# MCP23S17-v2.net
KiCad netlist of a schematic drawn in EAGLE
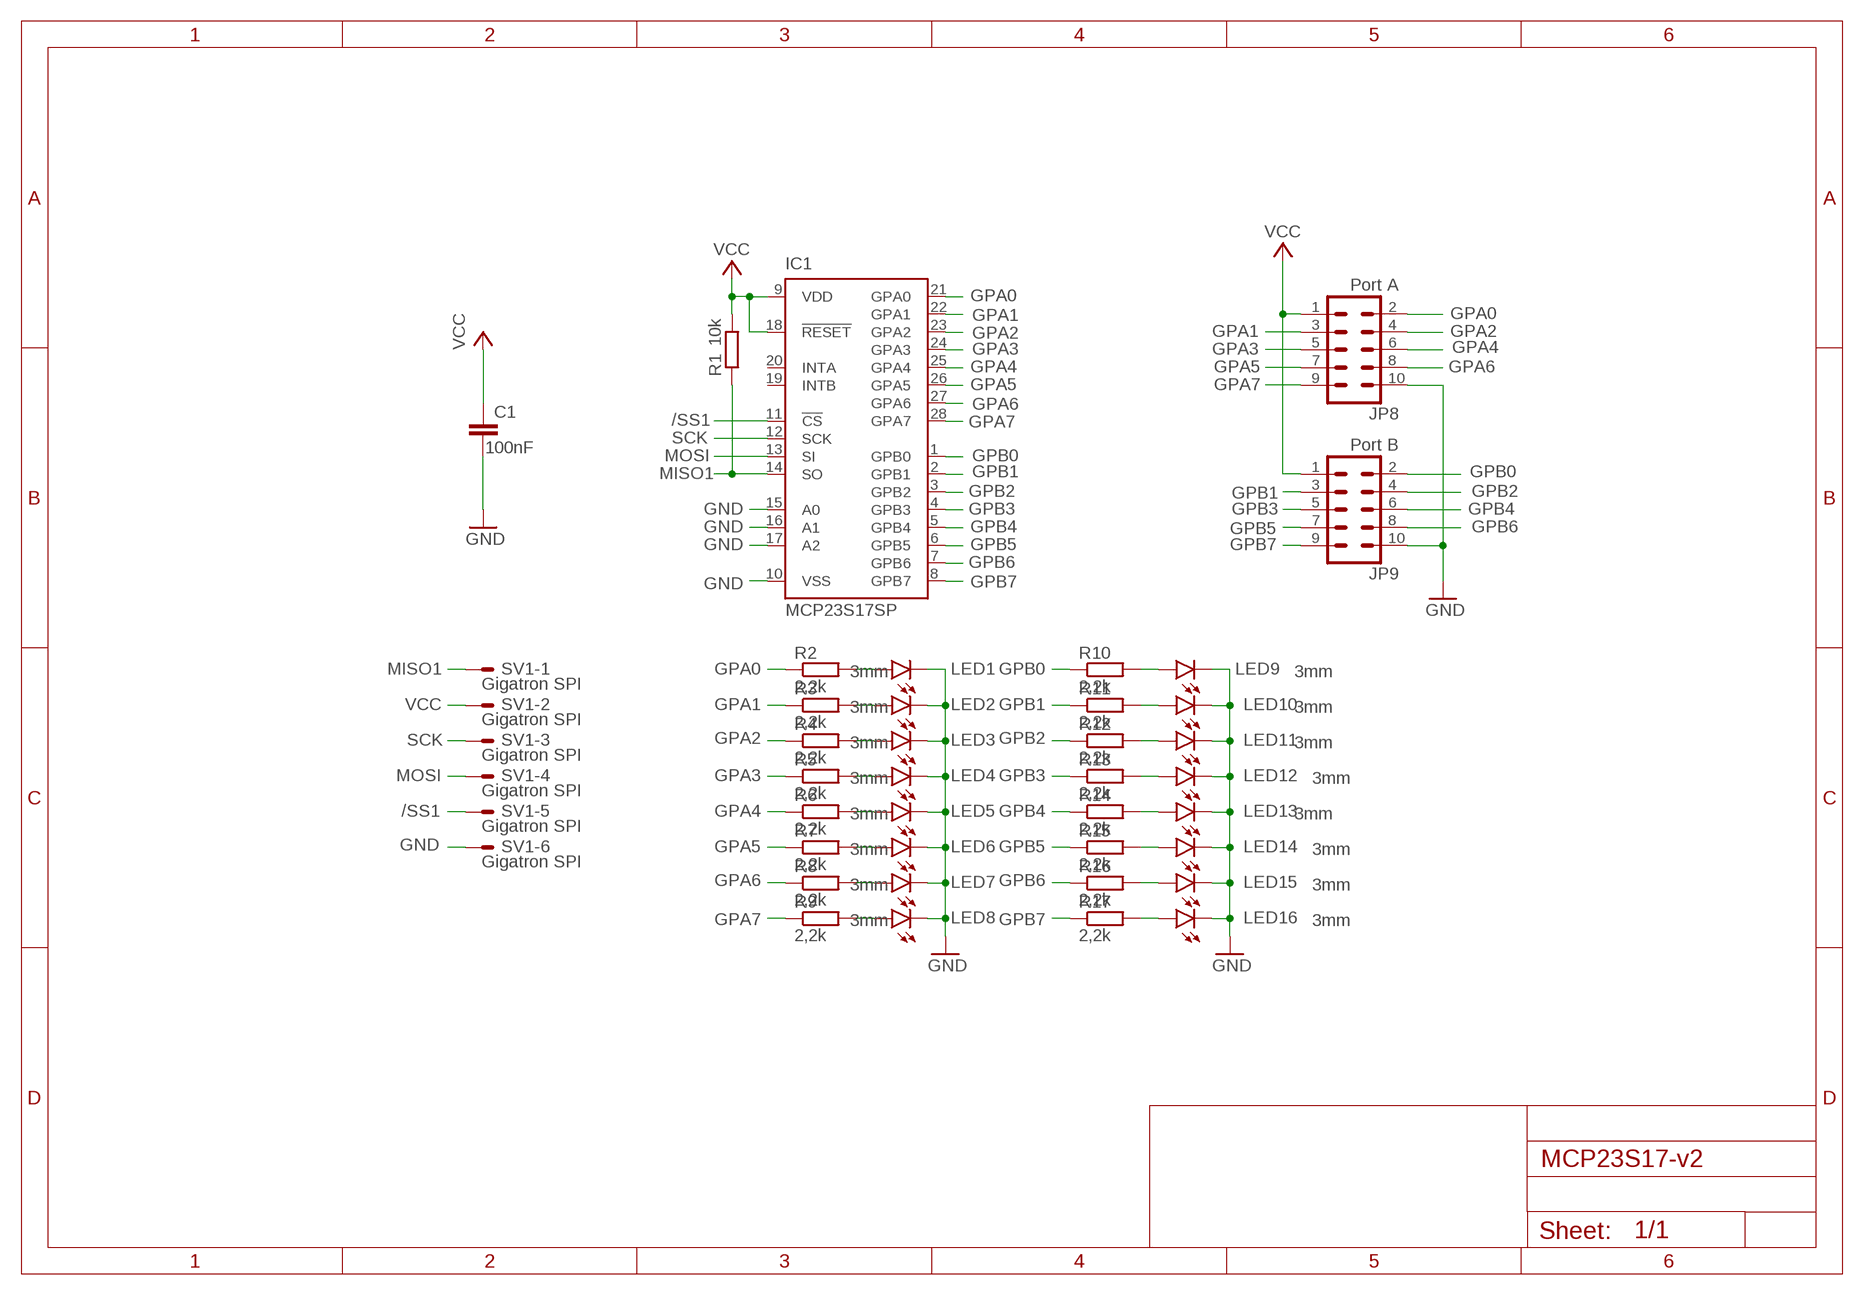
[diagram p0: schematic, sheet 1]

(export (version "E")
  (design (tool "Eeschema 10.0.6"))
  (components
    (comp (ref "C1")
      (value "100nF")
      (footprint "eagle-import:C5B2.5")
      (libsource (lib "eagle-import") (part "C5/2.5"))
    )
    (comp (ref "IC1")
      (value "MCP23S17SP")
      (footprint "eagle-import:DIL28-3")
      (fields (field (name "MF") "MICROCHIP") (field (name "MPN") "MCP23S17-E/SP"))
      (libsource (lib "eagle-import") (part "MCP23S17SP"))
    )
    (comp (ref "JP8")
      (value "Port A")
      (footprint "eagle-import:ML10")
      (libsource (lib "eagle-import") (part "ML10"))
    )
    (comp (ref "JP9")
      (value "Port B")
      (footprint "eagle-import:ML10")
      (libsource (lib "eagle-import") (part "ML10"))
    )
    (comp (ref "LED1")
      (value "3mm")
      (footprint "eagle-import:LED3MM")
      (libsource (lib "eagle-import") (part "LED3MM"))
    )
    (comp (ref "LED2")
      (value "3mm")
      (footprint "eagle-import:LED3MM")
      (libsource (lib "eagle-import") (part "LED3MM"))
    )
    (comp (ref "LED3")
      (value "3mm")
      (footprint "eagle-import:LED3MM")
      (libsource (lib "eagle-import") (part "LED3MM"))
    )
    (comp (ref "LED4")
      (value "3mm")
      (footprint "eagle-import:LED3MM")
      (libsource (lib "eagle-import") (part "LED3MM"))
    )
    (comp (ref "LED5")
      (value "3mm")
      (footprint "eagle-import:LED3MM")
      (libsource (lib "eagle-import") (part "LED3MM"))
    )
    (comp (ref "LED6")
      (value "3mm")
      (footprint "eagle-import:LED3MM")
      (libsource (lib "eagle-import") (part "LED3MM"))
    )
    (comp (ref "LED7")
      (value "3mm")
      (footprint "eagle-import:LED3MM")
      (libsource (lib "eagle-import") (part "LED3MM"))
    )
    (comp (ref "LED8")
      (value "3mm")
      (footprint "eagle-import:LED3MM")
      (libsource (lib "eagle-import") (part "LED3MM"))
    )
    (comp (ref "LED9")
      (value "3mm")
      (footprint "eagle-import:LED3MM")
      (libsource (lib "eagle-import") (part "LED3MM"))
    )
    (comp (ref "LED10")
      (value "3mm")
      (footprint "eagle-import:LED3MM")
      (libsource (lib "eagle-import") (part "LED3MM"))
    )
    (comp (ref "LED11")
      (value "3mm")
      (footprint "eagle-import:LED3MM")
      (libsource (lib "eagle-import") (part "LED3MM"))
    )
    (comp (ref "LED12")
      (value "3mm")
      (footprint "eagle-import:LED3MM")
      (libsource (lib "eagle-import") (part "LED3MM"))
    )
    (comp (ref "LED13")
      (value "3mm")
      (footprint "eagle-import:LED3MM")
      (libsource (lib "eagle-import") (part "LED3MM"))
    )
    (comp (ref "LED14")
      (value "3mm")
      (footprint "eagle-import:LED3MM")
      (libsource (lib "eagle-import") (part "LED3MM"))
    )
    (comp (ref "LED15")
      (value "3mm")
      (footprint "eagle-import:LED3MM")
      (libsource (lib "eagle-import") (part "LED3MM"))
    )
    (comp (ref "LED16")
      (value "3mm")
      (footprint "eagle-import:LED3MM")
      (libsource (lib "eagle-import") (part "LED3MM"))
    )
    (comp (ref "R1")
      (value "10k")
      (footprint "eagle-import:0207_10")
      (libsource (lib "eagle-import") (part "R-EU_0207/10"))
    )
    (comp (ref "R2")
      (value "2,2k")
      (footprint "eagle-import:0207_10")
      (libsource (lib "eagle-import") (part "R-EU_0207/10"))
    )
    (comp (ref "R3")
      (value "2,2k")
      (footprint "eagle-import:0207_10")
      (libsource (lib "eagle-import") (part "R-EU_0207/10"))
    )
    (comp (ref "R4")
      (value "2,2k")
      (footprint "eagle-import:0207_10")
      (libsource (lib "eagle-import") (part "R-EU_0207/10"))
    )
    (comp (ref "R5")
      (value "2,2k")
      (footprint "eagle-import:0207_10")
      (libsource (lib "eagle-import") (part "R-EU_0207/10"))
    )
    (comp (ref "R6")
      (value "2,2k")
      (footprint "eagle-import:0207_10")
      (libsource (lib "eagle-import") (part "R-EU_0207/10"))
    )
    (comp (ref "R7")
      (value "2,2k")
      (footprint "eagle-import:0207_10")
      (libsource (lib "eagle-import") (part "R-EU_0207/10"))
    )
    (comp (ref "R8")
      (value "2,2k")
      (footprint "eagle-import:0207_10")
      (libsource (lib "eagle-import") (part "R-EU_0207/10"))
    )
    (comp (ref "R9")
      (value "2,2k")
      (footprint "eagle-import:0207_10")
      (libsource (lib "eagle-import") (part "R-EU_0207/10"))
    )
    (comp (ref "R10")
      (value "2,2k")
      (footprint "eagle-import:0207_10")
      (libsource (lib "eagle-import") (part "R-EU_0207/10"))
    )
    (comp (ref "R11")
      (value "2,2k")
      (footprint "eagle-import:0207_10")
      (libsource (lib "eagle-import") (part "R-EU_0207/10"))
    )
    (comp (ref "R12")
      (value "2,2k")
      (footprint "eagle-import:0207_10")
      (libsource (lib "eagle-import") (part "R-EU_0207/10"))
    )
    (comp (ref "R13")
      (value "2,2k")
      (footprint "eagle-import:0207_10")
      (libsource (lib "eagle-import") (part "R-EU_0207/10"))
    )
    (comp (ref "R14")
      (value "2,2k")
      (footprint "eagle-import:0207_10")
      (libsource (lib "eagle-import") (part "R-EU_0207/10"))
    )
    (comp (ref "R15")
      (value "2,2k")
      (footprint "eagle-import:0207_10")
      (libsource (lib "eagle-import") (part "R-EU_0207/10"))
    )
    (comp (ref "R16")
      (value "2,2k")
      (footprint "eagle-import:0207_10")
      (libsource (lib "eagle-import") (part "R-EU_0207/10"))
    )
    (comp (ref "R17")
      (value "2,2k")
      (footprint "eagle-import:0207_10")
      (libsource (lib "eagle-import") (part "R-EU_0207/10"))
    )
    (comp (ref "SV1")
      (value "Gigatron SPI")
      (footprint "eagle-import:ML6")
      (libsource (lib "eagle-import") (part "ML6E"))
    )
  )
  (nets
    (net (code "1") (name "/GPA0") (class "Default")
      (node (ref "IC1") (pin "21") (pinfunction "GPA0_21") (pintype "bidirectional"))
      (node (ref "JP8") (pin "2") (pinfunction "2_2") (pintype "passive"))
      (node (ref "R2") (pin "1") (pinfunction "1_1") (pintype "passive"))
    )
    (net (code "2") (name "/GPA1") (class "Default")
      (node (ref "IC1") (pin "22") (pinfunction "GPA1_22") (pintype "bidirectional"))
      (node (ref "JP8") (pin "3") (pinfunction "3_3") (pintype "passive"))
      (node (ref "R3") (pin "1") (pinfunction "1_1") (pintype "passive"))
    )
    (net (code "3") (name "/GPA2") (class "Default")
      (node (ref "IC1") (pin "23") (pinfunction "GPA2_23") (pintype "bidirectional"))
      (node (ref "JP8") (pin "4") (pinfunction "4_4") (pintype "passive"))
      (node (ref "R4") (pin "1") (pinfunction "1_1") (pintype "passive"))
    )
    (net (code "4") (name "/GPA3") (class "Default")
      (node (ref "IC1") (pin "24") (pinfunction "GPA3_24") (pintype "bidirectional"))
      (node (ref "JP8") (pin "5") (pinfunction "5_5") (pintype "passive"))
      (node (ref "R5") (pin "1") (pinfunction "1_1") (pintype "passive"))
    )
    (net (code "5") (name "/GPA4") (class "Default")
      (node (ref "IC1") (pin "25") (pinfunction "GPA4_25") (pintype "bidirectional"))
      (node (ref "JP8") (pin "6") (pinfunction "6_6") (pintype "passive"))
      (node (ref "R6") (pin "1") (pinfunction "1_1") (pintype "passive"))
    )
    (net (code "6") (name "/GPA5") (class "Default")
      (node (ref "IC1") (pin "26") (pinfunction "GPA5_26") (pintype "bidirectional"))
      (node (ref "JP8") (pin "7") (pinfunction "7_7") (pintype "passive"))
      (node (ref "R7") (pin "1") (pinfunction "1_1") (pintype "passive"))
    )
    (net (code "7") (name "/GPA6") (class "Default")
      (node (ref "IC1") (pin "27") (pinfunction "GPA6_27") (pintype "bidirectional"))
      (node (ref "JP8") (pin "8") (pinfunction "8_8") (pintype "passive"))
      (node (ref "R8") (pin "1") (pinfunction "1_1") (pintype "passive"))
    )
    (net (code "8") (name "/GPA7") (class "Default")
      (node (ref "IC1") (pin "28") (pinfunction "GPA7_28") (pintype "bidirectional"))
      (node (ref "JP8") (pin "9") (pinfunction "9_9") (pintype "passive"))
      (node (ref "R9") (pin "1") (pinfunction "1_1") (pintype "passive"))
    )
    (net (code "9") (name "/GPB0") (class "Default")
      (node (ref "IC1") (pin "1") (pinfunction "GPB0_1") (pintype "bidirectional"))
      (node (ref "JP9") (pin "2") (pinfunction "2_2") (pintype "passive"))
      (node (ref "R10") (pin "1") (pinfunction "1_1") (pintype "passive"))
    )
    (net (code "10") (name "/GPB1") (class "Default")
      (node (ref "IC1") (pin "2") (pinfunction "GPB1_2") (pintype "bidirectional"))
      (node (ref "JP9") (pin "3") (pinfunction "3_3") (pintype "passive"))
      (node (ref "R11") (pin "1") (pinfunction "1_1") (pintype "passive"))
    )
    (net (code "11") (name "/GPB2") (class "Default")
      (node (ref "IC1") (pin "3") (pinfunction "GPB2_3") (pintype "bidirectional"))
      (node (ref "JP9") (pin "4") (pinfunction "4_4") (pintype "passive"))
      (node (ref "R12") (pin "1") (pinfunction "1_1") (pintype "passive"))
    )
    (net (code "12") (name "/GPB3") (class "Default")
      (node (ref "IC1") (pin "4") (pinfunction "GPB3_4") (pintype "bidirectional"))
      (node (ref "JP9") (pin "5") (pinfunction "5_5") (pintype "passive"))
      (node (ref "R13") (pin "1") (pinfunction "1_1") (pintype "passive"))
    )
    (net (code "13") (name "/GPB4") (class "Default")
      (node (ref "IC1") (pin "5") (pinfunction "GPB4_5") (pintype "bidirectional"))
      (node (ref "JP9") (pin "6") (pinfunction "6_6") (pintype "passive"))
      (node (ref "R14") (pin "1") (pinfunction "1_1") (pintype "passive"))
    )
    (net (code "14") (name "/GPB5") (class "Default")
      (node (ref "IC1") (pin "6") (pinfunction "GPB5_6") (pintype "bidirectional"))
      (node (ref "JP9") (pin "7") (pinfunction "7_7") (pintype "passive"))
      (node (ref "R15") (pin "1") (pinfunction "1_1") (pintype "passive"))
    )
    (net (code "15") (name "/GPB6") (class "Default")
      (node (ref "IC1") (pin "7") (pinfunction "GPB6_7") (pintype "bidirectional"))
      (node (ref "JP9") (pin "8") (pinfunction "8_8") (pintype "passive"))
      (node (ref "R16") (pin "1") (pinfunction "1_1") (pintype "passive"))
    )
    (net (code "16") (name "/GPB7") (class "Default")
      (node (ref "IC1") (pin "8") (pinfunction "GPB7_8") (pintype "bidirectional"))
      (node (ref "JP9") (pin "9") (pinfunction "9_9") (pintype "passive"))
      (node (ref "R17") (pin "1") (pinfunction "1_1") (pintype "passive"))
    )
    (net (code "17") (name "/MISO1") (class "Default")
      (node (ref "IC1") (pin "14") (pinfunction "SO_14") (pintype "output"))
      (node (ref "R1") (pin "1") (pinfunction "1_1") (pintype "passive"))
      (node (ref "SV1") (pin "1") (pinfunction "S_1") (pintype "passive"))
    )
    (net (code "18") (name "/MOSI") (class "Default")
      (node (ref "IC1") (pin "13") (pinfunction "SI_13") (pintype "input"))
      (node (ref "SV1") (pin "4") (pinfunction "S_4") (pintype "passive"))
    )
    (net (code "19") (name "/SCK") (class "Default")
      (node (ref "IC1") (pin "12") (pinfunction "SCK_12") (pintype "input"))
      (node (ref "SV1") (pin "3") (pinfunction "S_3") (pintype "passive"))
    )
    (net (code "20") (name "/{slash}SS1") (class "Default")
      (node (ref "IC1") (pin "11") (pinfunction "~{CS}_11") (pintype "input"))
      (node (ref "SV1") (pin "5") (pinfunction "S_5") (pintype "passive"))
    )
    (net (code "21") (name "GND") (class "Default")
      (node (ref "C1") (pin "2") (pinfunction "2_2") (pintype "passive"))
      (node (ref "IC1") (pin "10") (pinfunction "VSS_10") (pintype "power_in"))
      (node (ref "IC1") (pin "15") (pinfunction "A0_15") (pintype "input"))
      (node (ref "IC1") (pin "16") (pinfunction "A1_16") (pintype "input"))
      (node (ref "IC1") (pin "17") (pinfunction "A2_17") (pintype "input"))
      (node (ref "JP8") (pin "10") (pinfunction "10_10") (pintype "passive"))
      (node (ref "JP9") (pin "10") (pinfunction "10_10") (pintype "passive"))
      (node (ref "LED1") (pin "K") (pinfunction "C_K") (pintype "passive"))
      (node (ref "LED10") (pin "K") (pinfunction "C_K") (pintype "passive"))
      (node (ref "LED11") (pin "K") (pinfunction "C_K") (pintype "passive"))
      (node (ref "LED12") (pin "K") (pinfunction "C_K") (pintype "passive"))
      (node (ref "LED13") (pin "K") (pinfunction "C_K") (pintype "passive"))
      (node (ref "LED14") (pin "K") (pinfunction "C_K") (pintype "passive"))
      (node (ref "LED15") (pin "K") (pinfunction "C_K") (pintype "passive"))
      (node (ref "LED16") (pin "K") (pinfunction "C_K") (pintype "passive"))
      (node (ref "LED2") (pin "K") (pinfunction "C_K") (pintype "passive"))
      (node (ref "LED3") (pin "K") (pinfunction "C_K") (pintype "passive"))
      (node (ref "LED4") (pin "K") (pinfunction "C_K") (pintype "passive"))
      (node (ref "LED5") (pin "K") (pinfunction "C_K") (pintype "passive"))
      (node (ref "LED6") (pin "K") (pinfunction "C_K") (pintype "passive"))
      (node (ref "LED7") (pin "K") (pinfunction "C_K") (pintype "passive"))
      (node (ref "LED8") (pin "K") (pinfunction "C_K") (pintype "passive"))
      (node (ref "LED9") (pin "K") (pinfunction "C_K") (pintype "passive"))
      (node (ref "SV1") (pin "6") (pinfunction "S_6") (pintype "passive"))
    )
    (net (code "22") (name "Net-(LED1-PadA)") (class "Default")
      (node (ref "LED1") (pin "A") (pinfunction "A_A") (pintype "passive"))
      (node (ref "R2") (pin "2") (pinfunction "2_2") (pintype "passive"))
    )
    (net (code "23") (name "Net-(LED2-PadA)") (class "Default")
      (node (ref "LED2") (pin "A") (pinfunction "A_A") (pintype "passive"))
      (node (ref "R3") (pin "2") (pinfunction "2_2") (pintype "passive"))
    )
    (net (code "24") (name "Net-(LED3-PadA)") (class "Default")
      (node (ref "LED3") (pin "A") (pinfunction "A_A") (pintype "passive"))
      (node (ref "R4") (pin "2") (pinfunction "2_2") (pintype "passive"))
    )
    (net (code "25") (name "Net-(LED4-PadA)") (class "Default")
      (node (ref "LED4") (pin "A") (pinfunction "A_A") (pintype "passive"))
      (node (ref "R5") (pin "2") (pinfunction "2_2") (pintype "passive"))
    )
    (net (code "26") (name "Net-(LED5-PadA)") (class "Default")
      (node (ref "LED5") (pin "A") (pinfunction "A_A") (pintype "passive"))
      (node (ref "R6") (pin "2") (pinfunction "2_2") (pintype "passive"))
    )
    (net (code "27") (name "Net-(LED6-PadA)") (class "Default")
      (node (ref "LED6") (pin "A") (pinfunction "A_A") (pintype "passive"))
      (node (ref "R7") (pin "2") (pinfunction "2_2") (pintype "passive"))
    )
    (net (code "28") (name "Net-(LED7-PadA)") (class "Default")
      (node (ref "LED7") (pin "A") (pinfunction "A_A") (pintype "passive"))
      (node (ref "R8") (pin "2") (pinfunction "2_2") (pintype "passive"))
    )
    (net (code "29") (name "Net-(LED8-PadA)") (class "Default")
      (node (ref "LED8") (pin "A") (pinfunction "A_A") (pintype "passive"))
      (node (ref "R9") (pin "2") (pinfunction "2_2") (pintype "passive"))
    )
    (net (code "30") (name "Net-(LED9-PadA)") (class "Default")
      (node (ref "LED9") (pin "A") (pinfunction "A_A") (pintype "passive"))
      (node (ref "R10") (pin "2") (pinfunction "2_2") (pintype "passive"))
    )
    (net (code "31") (name "Net-(LED10-PadA)") (class "Default")
      (node (ref "LED10") (pin "A") (pinfunction "A_A") (pintype "passive"))
      (node (ref "R11") (pin "2") (pinfunction "2_2") (pintype "passive"))
    )
    (net (code "32") (name "Net-(LED11-PadA)") (class "Default")
      (node (ref "LED11") (pin "A") (pinfunction "A_A") (pintype "passive"))
      (node (ref "R12") (pin "2") (pinfunction "2_2") (pintype "passive"))
    )
    (net (code "33") (name "Net-(LED12-PadA)") (class "Default")
      (node (ref "LED12") (pin "A") (pinfunction "A_A") (pintype "passive"))
      (node (ref "R13") (pin "2") (pinfunction "2_2") (pintype "passive"))
    )
    (net (code "34") (name "Net-(LED13-PadA)") (class "Default")
      (node (ref "LED13") (pin "A") (pinfunction "A_A") (pintype "passive"))
      (node (ref "R14") (pin "2") (pinfunction "2_2") (pintype "passive"))
    )
    (net (code "35") (name "Net-(LED14-PadA)") (class "Default")
      (node (ref "LED14") (pin "A") (pinfunction "A_A") (pintype "passive"))
      (node (ref "R15") (pin "2") (pinfunction "2_2") (pintype "passive"))
    )
    (net (code "36") (name "Net-(LED15-PadA)") (class "Default")
      (node (ref "LED15") (pin "A") (pinfunction "A_A") (pintype "passive"))
      (node (ref "R16") (pin "2") (pinfunction "2_2") (pintype "passive"))
    )
    (net (code "37") (name "Net-(LED16-PadA)") (class "Default")
      (node (ref "LED16") (pin "A") (pinfunction "A_A") (pintype "passive"))
      (node (ref "R17") (pin "2") (pinfunction "2_2") (pintype "passive"))
    )
    (net (code "38") (name "VCC") (class "Default")
      (node (ref "C1") (pin "1") (pinfunction "1_1") (pintype "passive"))
      (node (ref "IC1") (pin "18") (pinfunction "~{RESET}_18") (pintype "input"))
      (node (ref "IC1") (pin "9") (pinfunction "VDD_9") (pintype "power_in"))
      (node (ref "JP8") (pin "1") (pinfunction "1_1") (pintype "passive"))
      (node (ref "JP9") (pin "1") (pinfunction "1_1") (pintype "passive"))
      (node (ref "R1") (pin "2") (pinfunction "2_2") (pintype "passive"))
      (node (ref "SV1") (pin "2") (pinfunction "S_2") (pintype "passive"))
    )
    (net (code "39") (name "unconnected-(IC1-INTA-Pad20)") (class "Default")
      (node (ref "IC1") (pin "20") (pinfunction "INTA_20") (pintype "output"))
    )
    (net (code "40") (name "unconnected-(IC1-INTB-Pad19)") (class "Default")
      (node (ref "IC1") (pin "19") (pinfunction "INTB_19") (pintype "output"))
    )
  )
)
